# stromversorgung.net
KiCad netlist of a schematic drawn in EAGLE
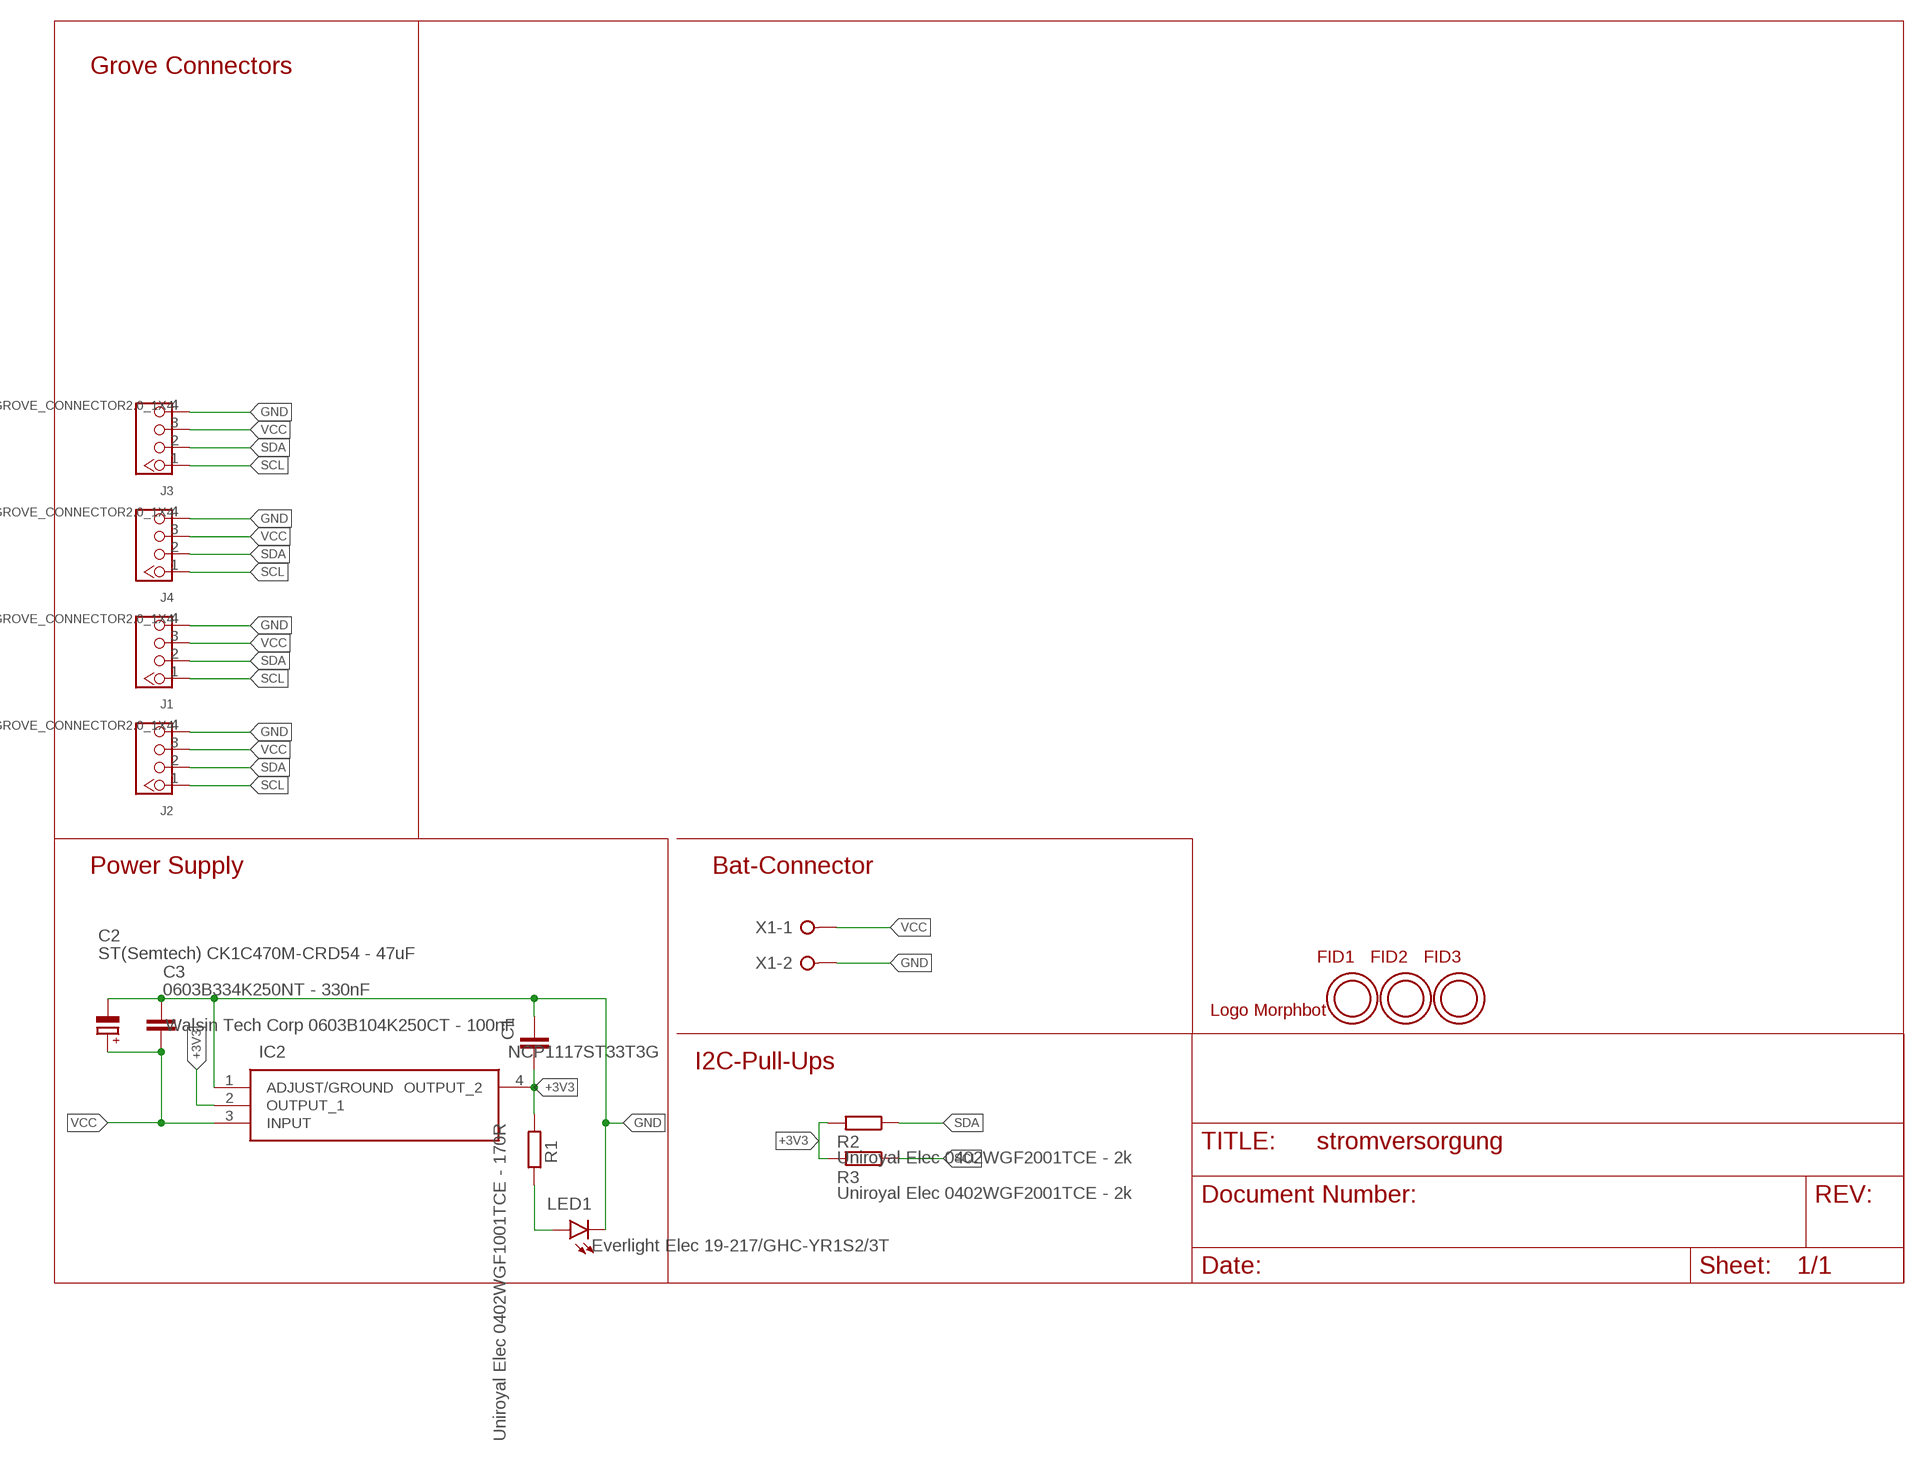
[diagram p0: schematic, sheet 1]

(export (version "E")
  (design (tool "Eeschema 10.0.6"))
  (components
    (comp (ref "C1")
      (value "Walsin Tech Corp 0603B104K250CT - 100nF")
      (footprint "eagle-import:C0603")
      (libsource (lib "eagle-import") (part "C-EUC0603"))
    )
    (comp (ref "C2")
      (value "ST(Semtech) CK1C470M-CRD54 - 47uF")
      (footprint "eagle-import:PANASONIC_C")
      (libsource (lib "eagle-import") (part "CPOL-EUC"))
    )
    (comp (ref "C3")
      (value "0603B334K250NT - 330nF")
      (footprint "eagle-import:C0603")
      (libsource (lib "eagle-import") (part "C-EUC0603"))
    )
    (comp (ref "FID1")
      (value "OPEN-PNP-FIDUCIAL")
      (footprint "eagle-import:OPEN-PNP-FIDUCIAL")
      (libsource (lib "eagle-import") (part "OPEN-PNP-FIDUCIAL"))
    )
    (comp (ref "FID2")
      (value "OPEN-PNP-FIDUCIAL")
      (footprint "eagle-import:OPEN-PNP-FIDUCIAL")
      (libsource (lib "eagle-import") (part "OPEN-PNP-FIDUCIAL"))
    )
    (comp (ref "FID3")
      (value "OPEN-PNP-FIDUCIAL")
      (footprint "eagle-import:OPEN-PNP-FIDUCIAL")
      (libsource (lib "eagle-import") (part "OPEN-PNP-FIDUCIAL"))
    )
    (comp (ref "IC2")
      (value "NCP1117ST33T3G")
      (footprint "eagle-import:SOT230P700X180-4N")
      (fields (field (name "MOUSER_PART_NUMBER") "863-NCP1117ST33T3G"))
      (libsource (lib "eagle-import") (part "NCP1117ST33T3G"))
    )
    (comp (ref "J1")
      (value "GROVE_CONNECTOR2.0_1X4")
      (footprint "eagle-import:2.0_1X4_STRAIGHT")
      (libsource (lib "eagle-import") (part "GROVE_CONNECTOR2.0_1X4"))
    )
    (comp (ref "J2")
      (value "GROVE_CONNECTOR2.0_1X4")
      (footprint "eagle-import:2.0_1X4_STRAIGHT")
      (libsource (lib "eagle-import") (part "GROVE_CONNECTOR2.0_1X4"))
    )
    (comp (ref "J3")
      (value "GROVE_CONNECTOR2.0_1X4")
      (footprint "eagle-import:2.0_1X4_STRAIGHT")
      (libsource (lib "eagle-import") (part "GROVE_CONNECTOR2.0_1X4"))
    )
    (comp (ref "J4")
      (value "GROVE_CONNECTOR2.0_1X4")
      (footprint "eagle-import:2.0_1X4_STRAIGHT")
      (libsource (lib "eagle-import") (part "GROVE_CONNECTOR2.0_1X4"))
    )
    (comp (ref "LED1")
      (value "Everlight Elec 19-217/GHC-YR1S2/3T")
      (footprint "eagle-import:CHIPLED_0603")
      (libsource (lib "eagle-import") (part "LEDCHIPLED_0603"))
    )
    (comp (ref "R1")
      (value "Uniroyal Elec 0402WGF1001TCE - 170R")
      (footprint "eagle-import:R0402")
      (libsource (lib "eagle-import") (part "R-EU_R0402"))
    )
    (comp (ref "R2")
      (value "Uniroyal Elec 0402WGF2001TCE - 2k")
      (footprint "eagle-import:R0402")
      (libsource (lib "eagle-import") (part "R-EU_R0402"))
    )
    (comp (ref "R3")
      (value "Uniroyal Elec 0402WGF2001TCE - 2k")
      (footprint "eagle-import:R0402")
      (libsource (lib "eagle-import") (part "R-EU_R0402"))
    )
    (comp (ref "U$1")
      (value "LOGO_MORPHBOT5MM")
      (footprint "eagle-import:LOGO_MORPHBOT")
      (libsource (lib "eagle-import") (part "LOGO_MORPHBOT5MM"))
    )
    (comp (ref "X1")
      (value "W237-02P")
      (footprint "eagle-import:W237-132")
      (libsource (lib "eagle-import") (part "W237-02P"))
    )
  )
  (nets
    (net (code "1") (name "+3V3") (class "Default")
      (node (ref "C1") (pin "1") (pinfunction "1_1") (pintype "passive"))
      (node (ref "IC2") (pin "2") (pinfunction "OUTPUT_1_2") (pintype "bidirectional"))
      (node (ref "IC2") (pin "4") (pinfunction "OUTPUT_2_4") (pintype "bidirectional"))
      (node (ref "R1") (pin "2") (pinfunction "2_2") (pintype "passive"))
      (node (ref "R2") (pin "2") (pinfunction "2_2") (pintype "passive"))
      (node (ref "R3") (pin "2") (pinfunction "2_2") (pintype "passive"))
    )
    (net (code "2") (name "GND") (class "Default")
      (node (ref "C1") (pin "2") (pinfunction "2_2") (pintype "passive"))
      (node (ref "C2") (pin "-") (pinfunction "-_-") (pintype "passive"))
      (node (ref "C3") (pin "1") (pinfunction "1_1") (pintype "passive"))
      (node (ref "IC2") (pin "1") (pinfunction "ADJUST/GROUND_1") (pintype "bidirectional"))
      (node (ref "J1") (pin "4") (pinfunction "4_4") (pintype "bidirectional"))
      (node (ref "J2") (pin "4") (pinfunction "4_4") (pintype "bidirectional"))
      (node (ref "J3") (pin "4") (pinfunction "4_4") (pintype "bidirectional"))
      (node (ref "J4") (pin "4") (pinfunction "4_4") (pintype "bidirectional"))
      (node (ref "LED1") (pin "C") (pinfunction "C_C") (pintype "passive"))
      (node (ref "X1") (pin "2") (pinfunction "KL_2") (pintype "passive"))
    )
    (net (code "3") (name "Net-(LED1-PadA)") (class "Default")
      (node (ref "LED1") (pin "A") (pinfunction "A_A") (pintype "passive"))
      (node (ref "R1") (pin "1") (pinfunction "1_1") (pintype "passive"))
    )
    (net (code "4") (name "SCL") (class "Default")
      (node (ref "J1") (pin "1") (pinfunction "1_1") (pintype "bidirectional"))
      (node (ref "J2") (pin "1") (pinfunction "1_1") (pintype "bidirectional"))
      (node (ref "J3") (pin "1") (pinfunction "1_1") (pintype "bidirectional"))
      (node (ref "J4") (pin "1") (pinfunction "1_1") (pintype "bidirectional"))
      (node (ref "R3") (pin "1") (pinfunction "1_1") (pintype "passive"))
    )
    (net (code "5") (name "SDA") (class "Default")
      (node (ref "J1") (pin "2") (pinfunction "2_2") (pintype "bidirectional"))
      (node (ref "J2") (pin "2") (pinfunction "2_2") (pintype "bidirectional"))
      (node (ref "J3") (pin "2") (pinfunction "2_2") (pintype "bidirectional"))
      (node (ref "J4") (pin "2") (pinfunction "2_2") (pintype "bidirectional"))
      (node (ref "R2") (pin "1") (pinfunction "1_1") (pintype "passive"))
    )
    (net (code "6") (name "VCC") (class "Default")
      (node (ref "C2") (pin "+") (pinfunction "+_+") (pintype "passive"))
      (node (ref "C3") (pin "2") (pinfunction "2_2") (pintype "passive"))
      (node (ref "IC2") (pin "3") (pinfunction "INPUT_3") (pintype "bidirectional"))
      (node (ref "J1") (pin "3") (pinfunction "3_3") (pintype "bidirectional"))
      (node (ref "J2") (pin "3") (pinfunction "3_3") (pintype "bidirectional"))
      (node (ref "J3") (pin "3") (pinfunction "3_3") (pintype "bidirectional"))
      (node (ref "J4") (pin "3") (pinfunction "3_3") (pintype "bidirectional"))
      (node (ref "X1") (pin "1") (pinfunction "KL_1") (pintype "passive"))
    )
  )
)
